# blinkm_mk2j2.net
KiCad netlist of a schematic drawn in EAGLE
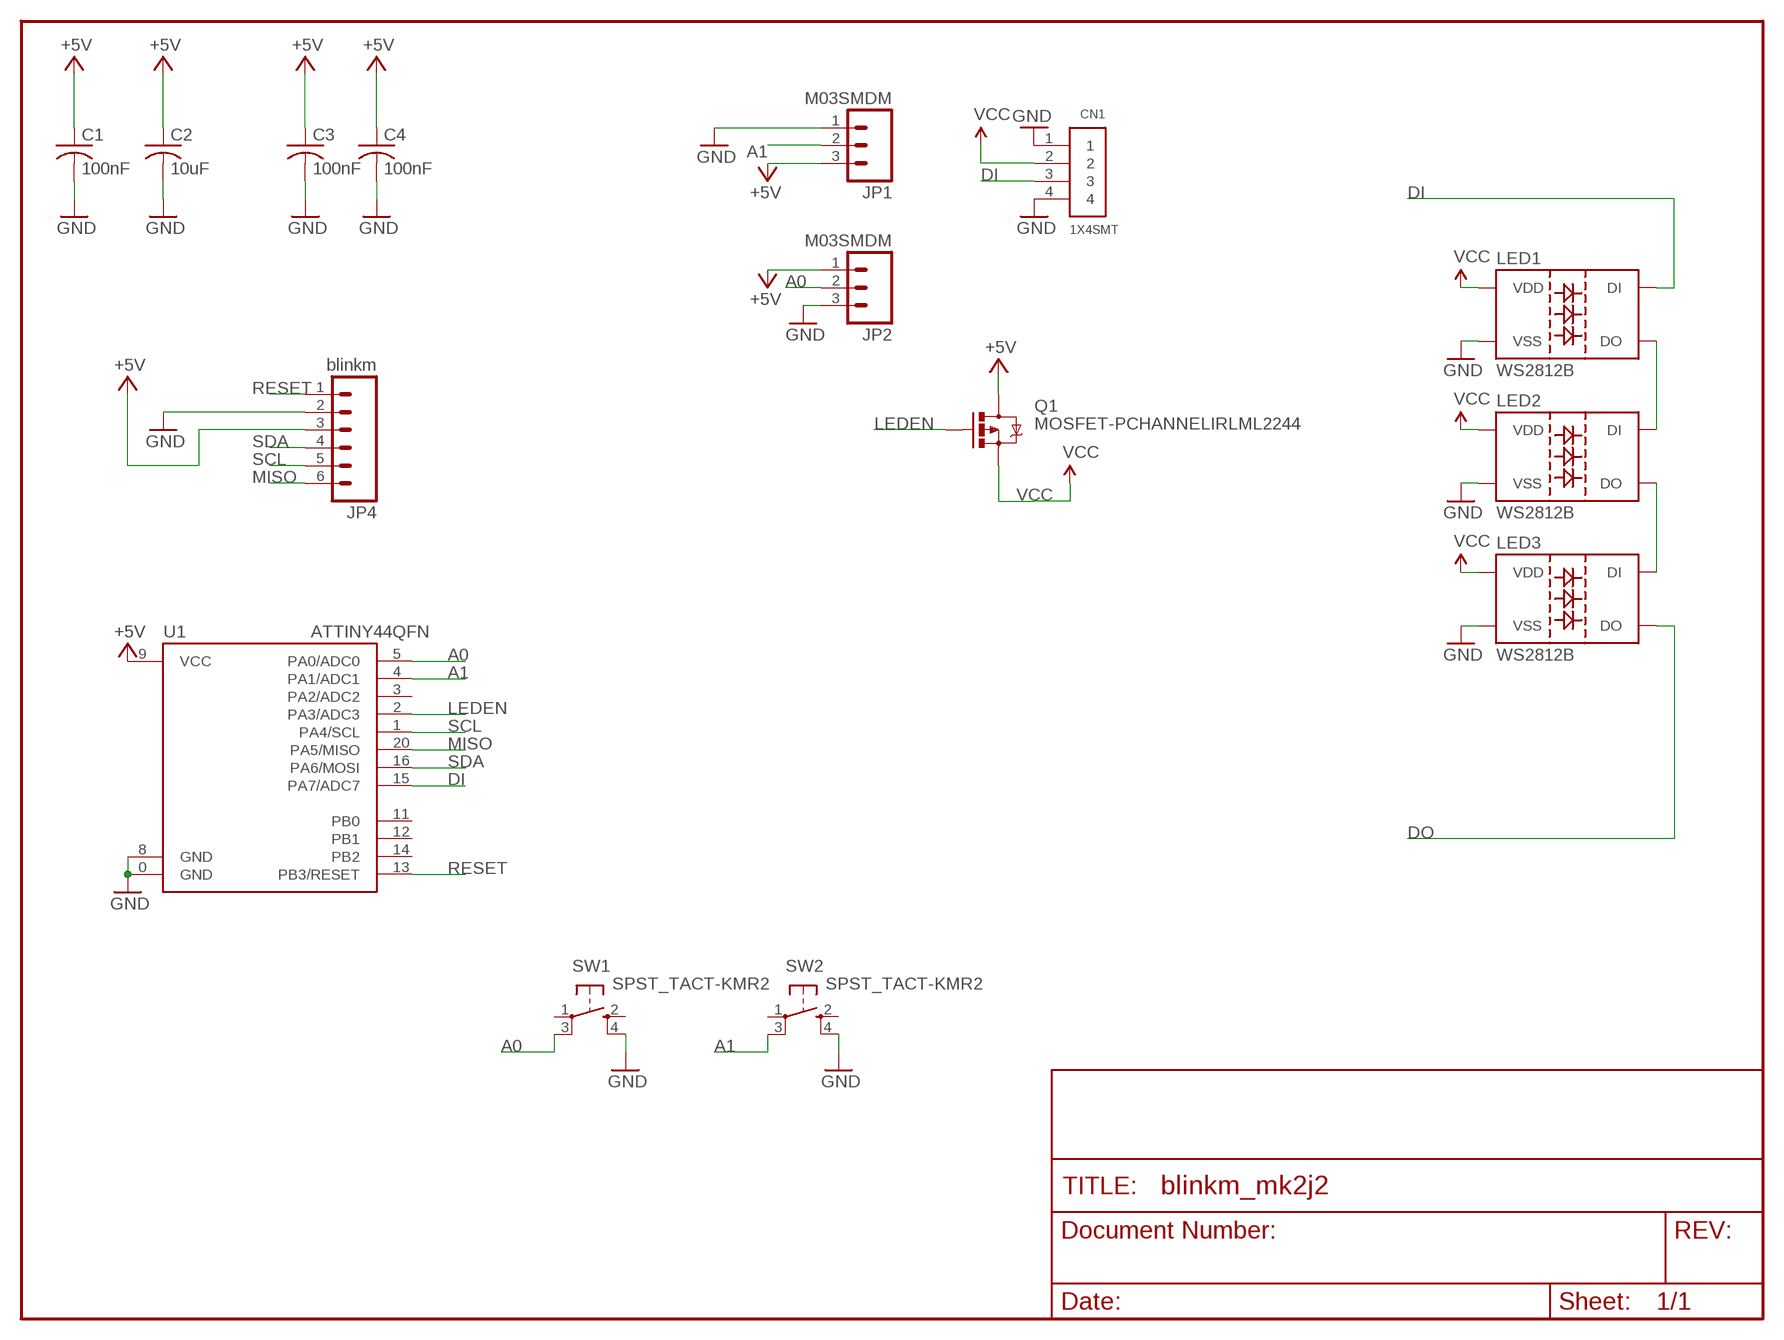
[diagram p0: schematic, sheet 1]

(export (version "E")
  (design (tool "Eeschema 10.0.6"))
  (components
    (comp (ref "C1")
      (value "100nF")
      (footprint "eagle-import:C0603")
      (libsource (lib "eagle-import") (part "C-USC0603"))
    )
    (comp (ref "C2")
      (value "10uF")
      (footprint "eagle-import:C0603")
      (libsource (lib "eagle-import") (part "C-USC0603"))
    )
    (comp (ref "C3")
      (value "100nF")
      (footprint "eagle-import:C0603")
      (libsource (lib "eagle-import") (part "C-USC0603"))
    )
    (comp (ref "C4")
      (value "100nF")
      (footprint "eagle-import:C0603")
      (libsource (lib "eagle-import") (part "C-USC0603"))
    )
    (comp (ref "CN1")
      (value "1X4SMT")
      (footprint "eagle-import:1X4-SMT")
      (libsource (lib "eagle-import") (part "1X4SMT"))
    )
    (comp (ref "JP1")
      (value "M03SMDM")
      (footprint "eagle-import:1X03-SMD-MINIMAL")
      (libsource (lib "eagle-import") (part "M03SMDM"))
    )
    (comp (ref "JP2")
      (value "M03SMDM")
      (footprint "eagle-import:1X03-SMD-MINIMAL")
      (libsource (lib "eagle-import") (part "M03SMDM"))
    )
    (comp (ref "JP4")
      (value "blinkm")
      (footprint "eagle-import:1X06_LOCK")
      (libsource (lib "eagle-import") (part "M06LOCK"))
    )
    (comp (ref "LED1")
      (value "WS2812B")
      (footprint "eagle-import:WS2812B")
      (libsource (lib "eagle-import") (part "WS2812B"))
    )
    (comp (ref "LED2")
      (value "WS2812B")
      (footprint "eagle-import:WS2812B")
      (libsource (lib "eagle-import") (part "WS2812B"))
    )
    (comp (ref "LED3")
      (value "WS2812B")
      (footprint "eagle-import:WS2812B")
      (libsource (lib "eagle-import") (part "WS2812B"))
    )
    (comp (ref "Q1")
      (value "MOSFET-PCHANNELIRLML2244")
      (footprint "eagle-import:SOT23-3")
      (libsource (lib "eagle-import") (part "MOSFET-PCHANNELIRLML2244"))
    )
    (comp (ref "SW1")
      (value "SPST_TACT-KMR2")
      (footprint "eagle-import:KMR2")
      (libsource (lib "eagle-import") (part "SPST_TACT-KMR2"))
    )
    (comp (ref "SW2")
      (value "SPST_TACT-KMR2")
      (footprint "eagle-import:KMR2")
      (libsource (lib "eagle-import") (part "SPST_TACT-KMR2"))
    )
    (comp (ref "U1")
      (value "ATTINY44QFN")
      (footprint "eagle-import:QFN20")
      (libsource (lib "eagle-import") (part "ATTINY24QFN"))
    )
  )
  (nets
    (net (code "1") (name "+5V") (class "Default")
      (node (ref "C1") (pin "1") (pinfunction "1_1") (pintype "passive"))
      (node (ref "C2") (pin "1") (pinfunction "1_1") (pintype "passive"))
      (node (ref "C3") (pin "1") (pinfunction "1_1") (pintype "passive"))
      (node (ref "C4") (pin "1") (pinfunction "1_1") (pintype "passive"))
      (node (ref "JP1") (pin "3") (pinfunction "3_3") (pintype "passive"))
      (node (ref "JP2") (pin "1") (pinfunction "1_1") (pintype "passive"))
      (node (ref "JP4") (pin "3") (pinfunction "3_3") (pintype "passive"))
      (node (ref "Q1") (pin "3") (pinfunction "D_3") (pintype "passive"))
      (node (ref "U1") (pin "9") (pinfunction "VCC_9") (pintype "bidirectional"))
    )
    (net (code "2") (name "/A0") (class "Default")
      (node (ref "JP2") (pin "2") (pinfunction "2_2") (pintype "passive"))
      (node (ref "SW1") (pin "3") (pinfunction "P1_3") (pintype "passive"))
      (node (ref "U1") (pin "5") (pinfunction "PA0/ADC0_5") (pintype "bidirectional"))
    )
    (net (code "3") (name "/A1") (class "Default")
      (node (ref "JP1") (pin "2") (pinfunction "2_2") (pintype "passive"))
      (node (ref "SW2") (pin "3") (pinfunction "P1_3") (pintype "passive"))
      (node (ref "U1") (pin "4") (pinfunction "PA1/ADC1_4") (pintype "bidirectional"))
    )
    (net (code "4") (name "/DI") (class "Default")
      (node (ref "CN1") (pin "3") (pinfunction "3_3") (pintype "bidirectional"))
      (node (ref "LED1") (pin "4") (pinfunction "DI_4") (pintype "bidirectional"))
      (node (ref "U1") (pin "15") (pinfunction "PA7/ADC7_15") (pintype "bidirectional"))
    )
    (net (code "5") (name "/DO") (class "Default")
      (node (ref "LED3") (pin "2") (pinfunction "DO_2") (pintype "bidirectional"))
    )
    (net (code "6") (name "/LEDEN") (class "Default")
      (node (ref "Q1") (pin "1") (pinfunction "G_1") (pintype "passive"))
      (node (ref "U1") (pin "2") (pinfunction "PA3/ADC3_2") (pintype "bidirectional"))
    )
    (net (code "7") (name "/MISO") (class "Default")
      (node (ref "JP4") (pin "6") (pinfunction "6_6") (pintype "passive"))
      (node (ref "U1") (pin "20") (pinfunction "PA5/MISO_20") (pintype "bidirectional"))
    )
    (net (code "8") (name "/RESET") (class "Default")
      (node (ref "JP4") (pin "1") (pinfunction "1_1") (pintype "passive"))
      (node (ref "U1") (pin "13") (pinfunction "PB3/RESET_13") (pintype "bidirectional"))
    )
    (net (code "9") (name "/SCL") (class "Default")
      (node (ref "JP4") (pin "5") (pinfunction "5_5") (pintype "passive"))
      (node (ref "U1") (pin "1") (pinfunction "PA4/SCL_1") (pintype "bidirectional"))
    )
    (net (code "10") (name "/SDA") (class "Default")
      (node (ref "JP4") (pin "4") (pinfunction "4_4") (pintype "passive"))
      (node (ref "U1") (pin "16") (pinfunction "PA6/MOSI_16") (pintype "bidirectional"))
    )
    (net (code "11") (name "GND") (class "Default")
      (node (ref "C1") (pin "2") (pinfunction "2_2") (pintype "passive"))
      (node (ref "C2") (pin "2") (pinfunction "2_2") (pintype "passive"))
      (node (ref "C3") (pin "2") (pinfunction "2_2") (pintype "passive"))
      (node (ref "C4") (pin "2") (pinfunction "2_2") (pintype "passive"))
      (node (ref "CN1") (pin "1") (pinfunction "1_1") (pintype "bidirectional"))
      (node (ref "CN1") (pin "4") (pinfunction "4_4") (pintype "bidirectional"))
      (node (ref "JP1") (pin "1") (pinfunction "1_1") (pintype "passive"))
      (node (ref "JP2") (pin "3") (pinfunction "3_3") (pintype "passive"))
      (node (ref "JP4") (pin "2") (pinfunction "2_2") (pintype "passive"))
      (node (ref "LED1") (pin "3") (pinfunction "VSS_3") (pintype "bidirectional"))
      (node (ref "LED2") (pin "3") (pinfunction "VSS_3") (pintype "bidirectional"))
      (node (ref "LED3") (pin "3") (pinfunction "VSS_3") (pintype "bidirectional"))
      (node (ref "SW1") (pin "4") (pinfunction "S1_4") (pintype "passive"))
      (node (ref "SW2") (pin "4") (pinfunction "S1_4") (pintype "passive"))
      (node (ref "U1") (pin "0") (pinfunction "GND_0") (pintype "bidirectional"))
      (node (ref "U1") (pin "8") (pinfunction "GND_8") (pintype "bidirectional"))
    )
    (net (code "12") (name "Net-(LED1-DO)") (class "Default")
      (node (ref "LED1") (pin "2") (pinfunction "DO_2") (pintype "bidirectional"))
      (node (ref "LED2") (pin "4") (pinfunction "DI_4") (pintype "bidirectional"))
    )
    (net (code "13") (name "Net-(LED2-DO)") (class "Default")
      (node (ref "LED2") (pin "2") (pinfunction "DO_2") (pintype "bidirectional"))
      (node (ref "LED3") (pin "4") (pinfunction "DI_4") (pintype "bidirectional"))
    )
    (net (code "14") (name "VCC") (class "Default")
      (node (ref "CN1") (pin "2") (pinfunction "2_2") (pintype "bidirectional"))
      (node (ref "LED1") (pin "1") (pinfunction "VDD_1") (pintype "bidirectional"))
      (node (ref "LED2") (pin "1") (pinfunction "VDD_1") (pintype "bidirectional"))
      (node (ref "LED3") (pin "1") (pinfunction "VDD_1") (pintype "bidirectional"))
      (node (ref "Q1") (pin "2") (pinfunction "S_2") (pintype "passive"))
    )
    (net (code "15") (name "unconnected-(SW1-P-Pad1)") (class "Default")
      (node (ref "SW1") (pin "1") (pinfunction "P_1") (pintype "passive"))
    )
    (net (code "16") (name "unconnected-(SW1-S-Pad2)") (class "Default")
      (node (ref "SW1") (pin "2") (pinfunction "S_2") (pintype "passive"))
    )
    (net (code "17") (name "unconnected-(SW2-P-Pad1)") (class "Default")
      (node (ref "SW2") (pin "1") (pinfunction "P_1") (pintype "passive"))
    )
    (net (code "18") (name "unconnected-(SW2-S-Pad2)") (class "Default")
      (node (ref "SW2") (pin "2") (pinfunction "S_2") (pintype "passive"))
    )
    (net (code "19") (name "unconnected-(U1-PA2{slash}ADC2-Pad3)") (class "Default")
      (node (ref "U1") (pin "3") (pinfunction "PA2/ADC2_3") (pintype "bidirectional"))
    )
    (net (code "20") (name "unconnected-(U1-PB0-Pad11)") (class "Default")
      (node (ref "U1") (pin "11") (pinfunction "PB0_11") (pintype "bidirectional"))
    )
    (net (code "21") (name "unconnected-(U1-PB1-Pad12)") (class "Default")
      (node (ref "U1") (pin "12") (pinfunction "PB1_12") (pintype "bidirectional"))
    )
    (net (code "22") (name "unconnected-(U1-PB2-Pad14)") (class "Default")
      (node (ref "U1") (pin "14") (pinfunction "PB2_14") (pintype "bidirectional"))
    )
  )
)
